# VGA_Test_Board.net
KiCad netlist of a schematic drawn in EAGLE
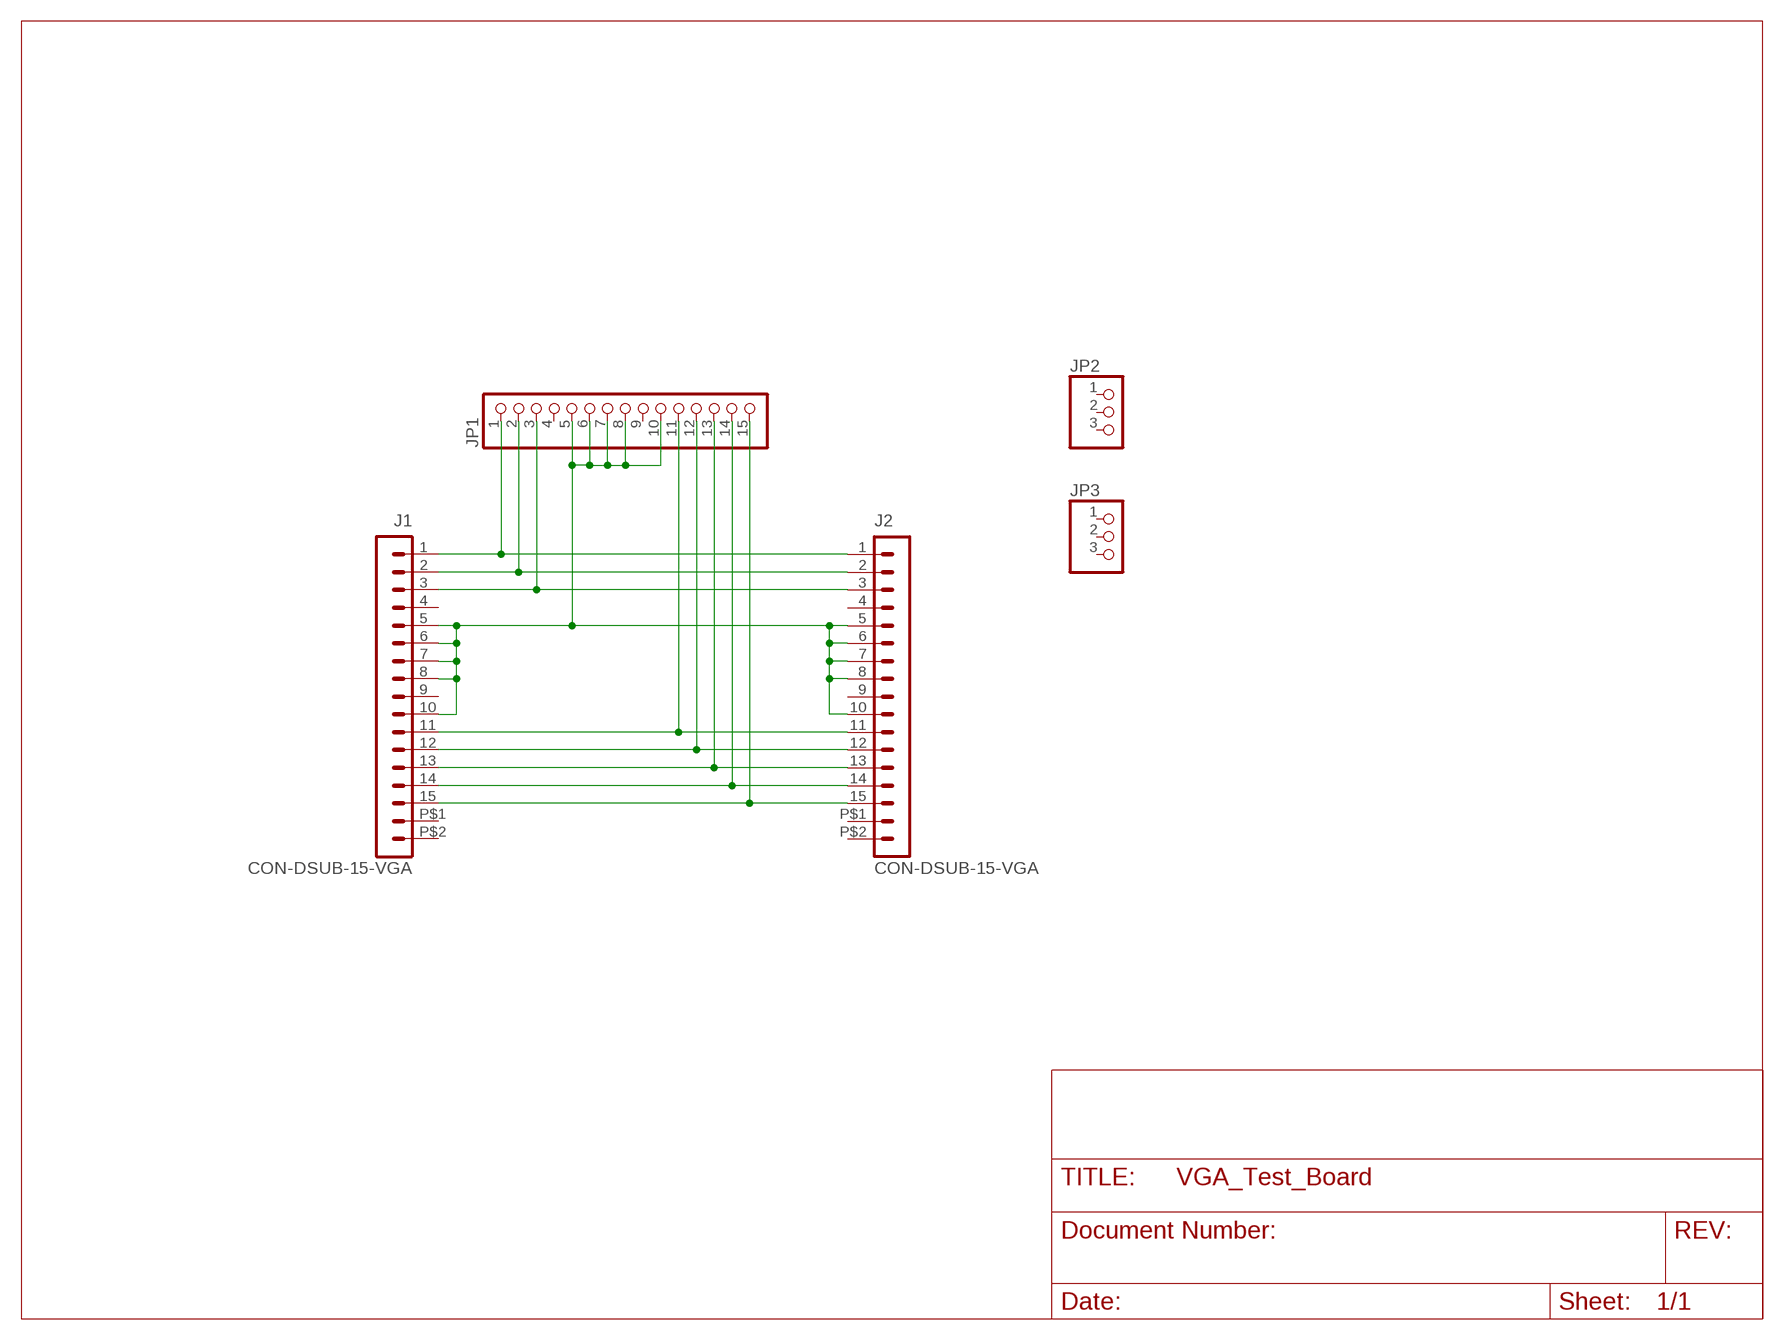
[diagram p0: schematic, sheet 1]

(export (version "E")
  (design (tool "Eeschema 10.0.6"))
  (components
    (comp (ref "J1")
      (value "CON-DSUB-15-VGA")
      (footprint "eagle-import:181-015-212-171")
      (libsource (lib "eagle-import") (part "CON-DSUB-15-VGA"))
    )
    (comp (ref "J2")
      (value "CON-DSUB-15-VGA")
      (footprint "eagle-import:181-015-212-171")
      (libsource (lib "eagle-import") (part "CON-DSUB-15-VGA"))
    )
    (comp (ref "JP1")
      (value "PINHD-1X15")
      (footprint "eagle-import:1X15")
      (libsource (lib "eagle-import") (part "PINHD-1X15"))
    )
    (comp (ref "JP2")
      (value "PINHD-1X3")
      (footprint "eagle-import:1X03")
      (libsource (lib "eagle-import") (part "PINHD-1X3"))
    )
    (comp (ref "JP3")
      (value "PINHD-1X3")
      (footprint "eagle-import:1X03")
      (libsource (lib "eagle-import") (part "PINHD-1X3"))
    )
  )
  (nets
    (net (code "1") (name "Net-(J1-Pad1)") (class "Default")
      (node (ref "J1") (pin "1") (pinfunction "1_1") (pintype "passive"))
      (node (ref "J2") (pin "1") (pinfunction "1_1") (pintype "passive"))
      (node (ref "JP1") (pin "1") (pinfunction "1_1") (pintype "passive"))
    )
    (net (code "2") (name "Net-(J1-Pad2)") (class "Default")
      (node (ref "J1") (pin "2") (pinfunction "2_2") (pintype "passive"))
      (node (ref "J2") (pin "2") (pinfunction "2_2") (pintype "passive"))
      (node (ref "JP1") (pin "2") (pinfunction "2_2") (pintype "passive"))
    )
    (net (code "3") (name "Net-(J1-Pad3)") (class "Default")
      (node (ref "J1") (pin "3") (pinfunction "3_3") (pintype "passive"))
      (node (ref "J2") (pin "3") (pinfunction "3_3") (pintype "passive"))
      (node (ref "JP1") (pin "3") (pinfunction "3_3") (pintype "passive"))
    )
    (net (code "4") (name "Net-(J1-Pad10)") (class "Default")
      (node (ref "J1") (pin "10") (pinfunction "10_10") (pintype "passive"))
      (node (ref "J1") (pin "5") (pinfunction "5_5") (pintype "passive"))
      (node (ref "J1") (pin "6") (pinfunction "6_6") (pintype "passive"))
      (node (ref "J1") (pin "7") (pinfunction "7_7") (pintype "passive"))
      (node (ref "J1") (pin "8") (pinfunction "8_8") (pintype "passive"))
      (node (ref "J2") (pin "10") (pinfunction "10_10") (pintype "passive"))
      (node (ref "J2") (pin "5") (pinfunction "5_5") (pintype "passive"))
      (node (ref "J2") (pin "6") (pinfunction "6_6") (pintype "passive"))
      (node (ref "J2") (pin "7") (pinfunction "7_7") (pintype "passive"))
      (node (ref "J2") (pin "8") (pinfunction "8_8") (pintype "passive"))
      (node (ref "JP1") (pin "10") (pinfunction "10_10") (pintype "passive"))
      (node (ref "JP1") (pin "5") (pinfunction "5_5") (pintype "passive"))
      (node (ref "JP1") (pin "6") (pinfunction "6_6") (pintype "passive"))
      (node (ref "JP1") (pin "7") (pinfunction "7_7") (pintype "passive"))
      (node (ref "JP1") (pin "8") (pinfunction "8_8") (pintype "passive"))
    )
    (net (code "5") (name "Net-(J1-Pad11)") (class "Default")
      (node (ref "J1") (pin "11") (pinfunction "11_11") (pintype "passive"))
      (node (ref "J2") (pin "11") (pinfunction "11_11") (pintype "passive"))
      (node (ref "JP1") (pin "11") (pinfunction "11_11") (pintype "passive"))
    )
    (net (code "6") (name "Net-(J1-Pad12)") (class "Default")
      (node (ref "J1") (pin "12") (pinfunction "12_12") (pintype "passive"))
      (node (ref "J2") (pin "12") (pinfunction "12_12") (pintype "passive"))
      (node (ref "JP1") (pin "12") (pinfunction "12_12") (pintype "passive"))
    )
    (net (code "7") (name "Net-(J1-Pad13)") (class "Default")
      (node (ref "J1") (pin "13") (pinfunction "13_13") (pintype "passive"))
      (node (ref "J2") (pin "13") (pinfunction "13_13") (pintype "passive"))
      (node (ref "JP1") (pin "13") (pinfunction "13_13") (pintype "passive"))
    )
    (net (code "8") (name "Net-(J1-Pad14)") (class "Default")
      (node (ref "J1") (pin "14") (pinfunction "14_14") (pintype "passive"))
      (node (ref "J2") (pin "14") (pinfunction "14_14") (pintype "passive"))
      (node (ref "JP1") (pin "14") (pinfunction "14_14") (pintype "passive"))
    )
    (net (code "9") (name "Net-(J1-Pad15)") (class "Default")
      (node (ref "J1") (pin "15") (pinfunction "15_15") (pintype "passive"))
      (node (ref "J2") (pin "15") (pinfunction "15_15") (pintype "passive"))
      (node (ref "JP1") (pin "15") (pinfunction "15_15") (pintype "passive"))
    )
    (net (code "10") (name "unconnected-(J1-16-PadP$1)") (class "Default")
      (node (ref "J1") (pin "P$1") (pinfunction "16_P$1") (pintype "passive"))
    )
    (net (code "11") (name "unconnected-(J1-17-PadP$2)") (class "Default")
      (node (ref "J1") (pin "P$2") (pinfunction "17_P$2") (pintype "passive"))
    )
    (net (code "12") (name "unconnected-(J1-Pad4)") (class "Default")
      (node (ref "J1") (pin "4") (pinfunction "4_4") (pintype "passive"))
    )
    (net (code "13") (name "unconnected-(J1-Pad9)") (class "Default")
      (node (ref "J1") (pin "9") (pinfunction "9_9") (pintype "passive"))
    )
    (net (code "14") (name "unconnected-(J2-16-PadP$1)") (class "Default")
      (node (ref "J2") (pin "P$1") (pinfunction "16_P$1") (pintype "passive"))
    )
    (net (code "15") (name "unconnected-(J2-17-PadP$2)") (class "Default")
      (node (ref "J2") (pin "P$2") (pinfunction "17_P$2") (pintype "passive"))
    )
    (net (code "16") (name "unconnected-(J2-Pad4)") (class "Default")
      (node (ref "J2") (pin "4") (pinfunction "4_4") (pintype "passive"))
    )
    (net (code "17") (name "unconnected-(J2-Pad9)") (class "Default")
      (node (ref "J2") (pin "9") (pinfunction "9_9") (pintype "passive"))
    )
    (net (code "18") (name "unconnected-(JP1-Pad4)") (class "Default")
      (node (ref "JP1") (pin "4") (pinfunction "4_4") (pintype "passive"))
    )
    (net (code "19") (name "unconnected-(JP1-Pad9)") (class "Default")
      (node (ref "JP1") (pin "9") (pinfunction "9_9") (pintype "passive"))
    )
    (net (code "20") (name "unconnected-(JP2-Pad1)") (class "Default")
      (node (ref "JP2") (pin "1") (pinfunction "1_1") (pintype "passive"))
    )
    (net (code "21") (name "unconnected-(JP2-Pad2)") (class "Default")
      (node (ref "JP2") (pin "2") (pinfunction "2_2") (pintype "passive"))
    )
    (net (code "22") (name "unconnected-(JP2-Pad3)") (class "Default")
      (node (ref "JP2") (pin "3") (pinfunction "3_3") (pintype "passive"))
    )
    (net (code "23") (name "unconnected-(JP3-Pad1)") (class "Default")
      (node (ref "JP3") (pin "1") (pinfunction "1_1") (pintype "passive"))
    )
    (net (code "24") (name "unconnected-(JP3-Pad2)") (class "Default")
      (node (ref "JP3") (pin "2") (pinfunction "2_2") (pintype "passive"))
    )
    (net (code "25") (name "unconnected-(JP3-Pad3)") (class "Default")
      (node (ref "JP3") (pin "3") (pinfunction "3_3") (pintype "passive"))
    )
  )
)
